# Flexy.net
KiCad netlist of a schematic drawn in Altium Designer
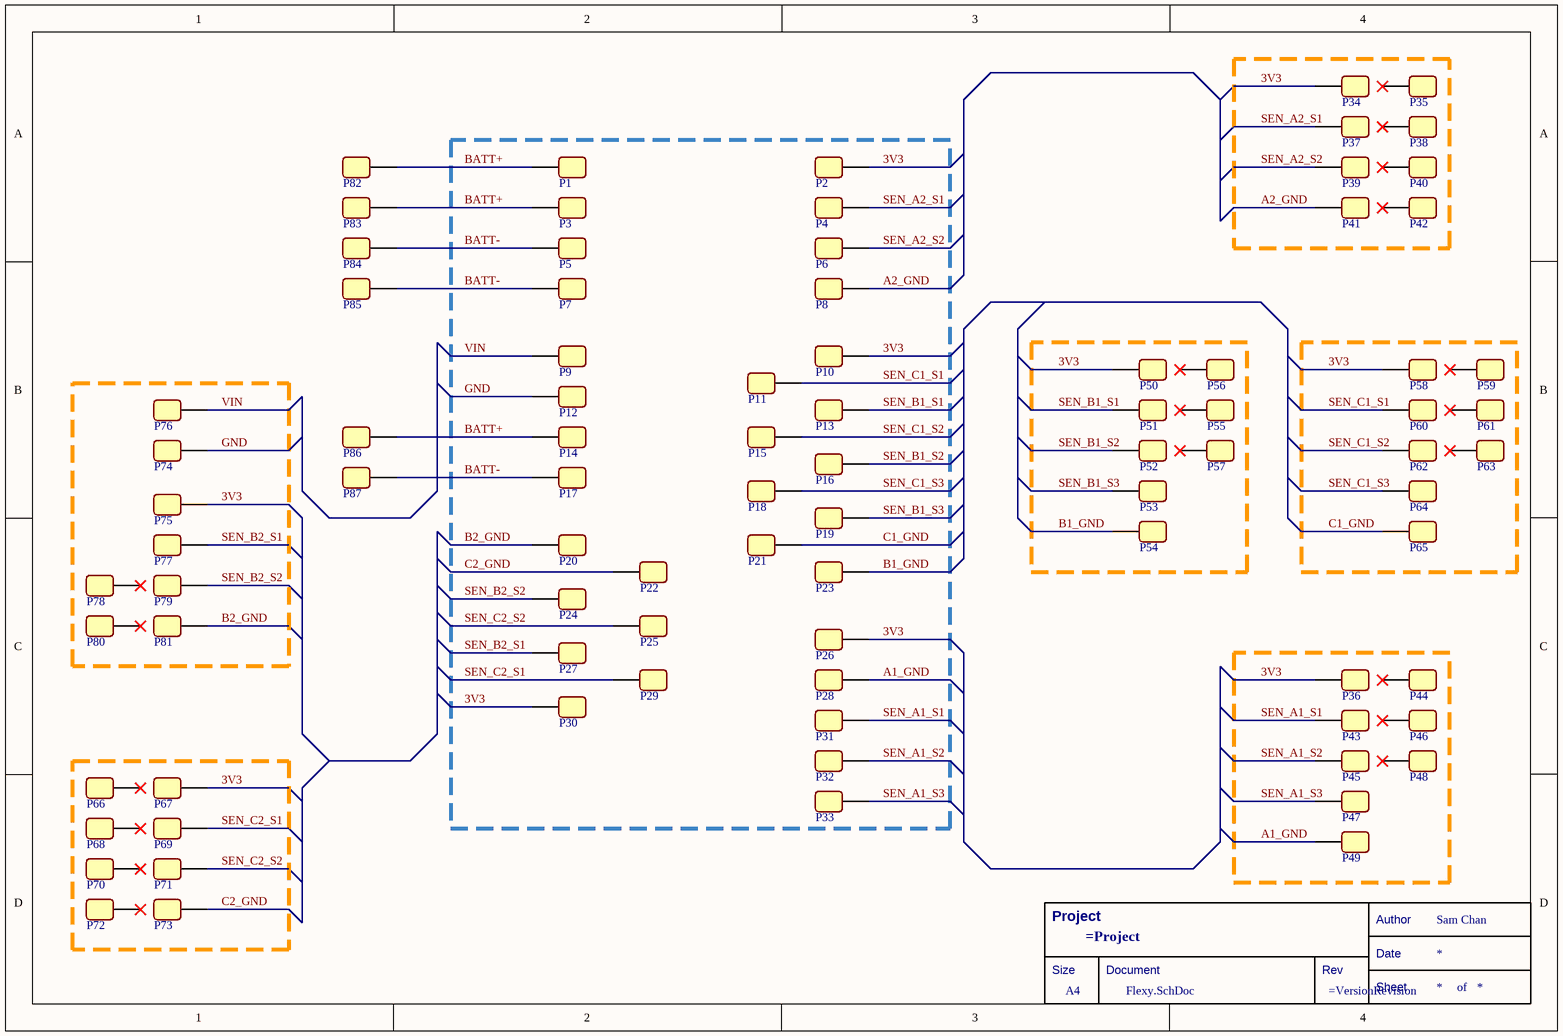
[diagram p0: Flexy.SchDoc]

(export (version "E")
  (design (tool "Eeschema 10.0.6"))
  (components
    (comp (ref "*")
      (value "Title Block")
      (description "Standard Title Block")
      (libsource (lib "Cube Library") (part "Title Block"))
    )
    (comp (ref "P1")
      (value "PAD_4")
      (footprint "PAD_0.5X1MM")
      (description "a Rec pad, 0.5X1mm")
      (libsource (lib "Cube Library") (part "PAD_4"))
    )
    (comp (ref "P2")
      (value "PAD_4")
      (footprint "PAD_0.5X1MM")
      (description "a Rec pad, 0.5X1mm")
      (libsource (lib "Cube Library") (part "PAD_4"))
    )
    (comp (ref "P3")
      (value "PAD_4")
      (footprint "PAD_0.5X1MM")
      (description "a Rec pad, 0.5X1mm")
      (libsource (lib "Cube Library") (part "PAD_4"))
    )
    (comp (ref "P4")
      (value "PAD_4")
      (footprint "PAD_0.5X1MM")
      (description "a Rec pad, 0.5X1mm")
      (libsource (lib "Cube Library") (part "PAD_4"))
    )
    (comp (ref "P5")
      (value "PAD_4")
      (footprint "PAD_0.5X1MM")
      (description "a Rec pad, 0.5X1mm")
      (libsource (lib "Cube Library") (part "PAD_4"))
    )
    (comp (ref "P6")
      (value "PAD_4")
      (footprint "PAD_0.5X1MM")
      (description "a Rec pad, 0.5X1mm")
      (libsource (lib "Cube Library") (part "PAD_4"))
    )
    (comp (ref "P7")
      (value "PAD_4")
      (footprint "PAD_0.5X1MM")
      (description "a Rec pad, 0.5X1mm")
      (libsource (lib "Cube Library") (part "PAD_4"))
    )
    (comp (ref "P8")
      (value "PAD_4")
      (footprint "PAD_0.5X1MM")
      (description "a Rec pad, 0.5X1mm")
      (libsource (lib "Cube Library") (part "PAD_4"))
    )
    (comp (ref "P9")
      (value "PAD_4")
      (footprint "PAD_0.5X1MM")
      (description "a Rec pad, 0.5X1mm")
      (libsource (lib "Cube Library") (part "PAD_4"))
    )
    (comp (ref "P10")
      (value "PAD_4")
      (footprint "PAD_0.5X1MM")
      (description "a Rec pad, 0.5X1mm")
      (libsource (lib "Cube Library") (part "PAD_4"))
    )
    (comp (ref "P11")
      (value "PAD_4")
      (footprint "PAD_0.5X1MM")
      (description "a Rec pad, 0.5X1mm")
      (libsource (lib "Cube Library") (part "PAD_4"))
    )
    (comp (ref "P12")
      (value "PAD_4")
      (footprint "PAD_0.5X1MM")
      (description "a Rec pad, 0.5X1mm")
      (libsource (lib "Cube Library") (part "PAD_4"))
    )
    (comp (ref "P13")
      (value "PAD_4")
      (footprint "PAD_0.5X1MM")
      (description "a Rec pad, 0.5X1mm")
      (libsource (lib "Cube Library") (part "PAD_4"))
    )
    (comp (ref "P14")
      (value "PAD_4")
      (footprint "PAD_0.5X1MM")
      (description "a Rec pad, 0.5X1mm")
      (libsource (lib "Cube Library") (part "PAD_4"))
    )
    (comp (ref "P15")
      (value "PAD_4")
      (footprint "PAD_0.5X1MM")
      (description "a Rec pad, 0.5X1mm")
      (libsource (lib "Cube Library") (part "PAD_4"))
    )
    (comp (ref "P16")
      (value "PAD_4")
      (footprint "PAD_0.5X1MM")
      (description "a Rec pad, 0.5X1mm")
      (libsource (lib "Cube Library") (part "PAD_4"))
    )
    (comp (ref "P17")
      (value "PAD_4")
      (footprint "PAD_0.5X1MM")
      (description "a Rec pad, 0.5X1mm")
      (libsource (lib "Cube Library") (part "PAD_4"))
    )
    (comp (ref "P18")
      (value "PAD_4")
      (footprint "PAD_0.5X1MM")
      (description "a Rec pad, 0.5X1mm")
      (libsource (lib "Cube Library") (part "PAD_4"))
    )
    (comp (ref "P19")
      (value "PAD_4")
      (footprint "PAD_0.5X1MM")
      (description "a Rec pad, 0.5X1mm")
      (libsource (lib "Cube Library") (part "PAD_4"))
    )
    (comp (ref "P20")
      (value "PAD_4")
      (footprint "PAD_0.5X1MM")
      (description "a Rec pad, 0.5X1mm")
      (libsource (lib "Cube Library") (part "PAD_4"))
    )
    (comp (ref "P21")
      (value "PAD_4")
      (footprint "PAD_0.5X1MM")
      (description "a Rec pad, 0.5X1mm")
      (libsource (lib "Cube Library") (part "PAD_4"))
    )
    (comp (ref "P22")
      (value "PAD_4")
      (footprint "PAD_0.5X1MM")
      (description "a Rec pad, 0.5X1mm")
      (libsource (lib "Cube Library") (part "PAD_4"))
    )
    (comp (ref "P23")
      (value "PAD_4")
      (footprint "PAD_0.5X1MM")
      (description "a Rec pad, 0.5X1mm")
      (libsource (lib "Cube Library") (part "PAD_4"))
    )
    (comp (ref "P24")
      (value "PAD_4")
      (footprint "PAD_0.5X1MM")
      (description "a Rec pad, 0.5X1mm")
      (libsource (lib "Cube Library") (part "PAD_4"))
    )
    (comp (ref "P25")
      (value "PAD_4")
      (footprint "PAD_0.5X1MM")
      (description "a Rec pad, 0.5X1mm")
      (libsource (lib "Cube Library") (part "PAD_4"))
    )
    (comp (ref "P26")
      (value "PAD_4")
      (footprint "PAD_0.5X1MM")
      (description "a Rec pad, 0.5X1mm")
      (libsource (lib "Cube Library") (part "PAD_4"))
    )
    (comp (ref "P27")
      (value "PAD_4")
      (footprint "PAD_0.5X1MM")
      (description "a Rec pad, 0.5X1mm")
      (libsource (lib "Cube Library") (part "PAD_4"))
    )
    (comp (ref "P28")
      (value "PAD_4")
      (footprint "PAD_0.5X1MM")
      (description "a Rec pad, 0.5X1mm")
      (libsource (lib "Cube Library") (part "PAD_4"))
    )
    (comp (ref "P29")
      (value "PAD_4")
      (footprint "PAD_0.5X1MM")
      (description "a Rec pad, 0.5X1mm")
      (libsource (lib "Cube Library") (part "PAD_4"))
    )
    (comp (ref "P30")
      (value "PAD_4")
      (footprint "PAD_0.5X1MM")
      (description "a Rec pad, 0.5X1mm")
      (libsource (lib "Cube Library") (part "PAD_4"))
    )
    (comp (ref "P31")
      (value "PAD_4")
      (footprint "PAD_0.5X1MM")
      (description "a Rec pad, 0.5X1mm")
      (libsource (lib "Cube Library") (part "PAD_4"))
    )
    (comp (ref "P32")
      (value "PAD_4")
      (footprint "PAD_0.5X1MM")
      (description "a Rec pad, 0.5X1mm")
      (libsource (lib "Cube Library") (part "PAD_4"))
    )
    (comp (ref "P33")
      (value "PAD_4")
      (footprint "PAD_0.5X1MM")
      (description "a Rec pad, 0.5X1mm")
      (libsource (lib "Cube Library") (part "PAD_4"))
    )
    (comp (ref "P34")
      (value "PAD_4")
      (footprint "PAD_0.5X1MM")
      (description "a Rec pad, 0.5X1mm")
      (libsource (lib "Cube Library") (part "PAD_4"))
    )
    (comp (ref "P35")
      (value "PAD_4")
      (footprint "PAD_0.5X1MM")
      (description "a Rec pad, 0.5X1mm")
      (libsource (lib "Cube Library") (part "PAD_4"))
    )
    (comp (ref "P36")
      (value "PAD_4")
      (footprint "PAD_0.5X1MM")
      (description "a Rec pad, 0.5X1mm")
      (libsource (lib "Cube Library") (part "PAD_4"))
    )
    (comp (ref "P37")
      (value "PAD_4")
      (footprint "PAD_0.5X1MM")
      (description "a Rec pad, 0.5X1mm")
      (libsource (lib "Cube Library") (part "PAD_4"))
    )
    (comp (ref "P38")
      (value "PAD_4")
      (footprint "PAD_0.5X1MM")
      (description "a Rec pad, 0.5X1mm")
      (libsource (lib "Cube Library") (part "PAD_4"))
    )
    (comp (ref "P39")
      (value "PAD_4")
      (footprint "PAD_0.5X1MM")
      (description "a Rec pad, 0.5X1mm")
      (libsource (lib "Cube Library") (part "PAD_4"))
    )
    (comp (ref "P40")
      (value "PAD_4")
      (footprint "PAD_0.5X1MM")
      (description "a Rec pad, 0.5X1mm")
      (libsource (lib "Cube Library") (part "PAD_4"))
    )
    (comp (ref "P41")
      (value "PAD_4")
      (footprint "PAD_0.5X1MM")
      (description "a Rec pad, 0.5X1mm")
      (libsource (lib "Cube Library") (part "PAD_4"))
    )
    (comp (ref "P42")
      (value "PAD_4")
      (footprint "PAD_0.5X1MM")
      (description "a Rec pad, 0.5X1mm")
      (libsource (lib "Cube Library") (part "PAD_4"))
    )
    (comp (ref "P43")
      (value "PAD_4")
      (footprint "PAD_0.5X1MM")
      (description "a Rec pad, 0.5X1mm")
      (libsource (lib "Cube Library") (part "PAD_4"))
    )
    (comp (ref "P44")
      (value "PAD_4")
      (footprint "PAD_0.5X1MM")
      (description "a Rec pad, 0.5X1mm")
      (libsource (lib "Cube Library") (part "PAD_4"))
    )
    (comp (ref "P45")
      (value "PAD_4")
      (footprint "PAD_0.5X1MM")
      (description "a Rec pad, 0.5X1mm")
      (libsource (lib "Cube Library") (part "PAD_4"))
    )
    (comp (ref "P46")
      (value "PAD_4")
      (footprint "PAD_0.5X1MM")
      (description "a Rec pad, 0.5X1mm")
      (libsource (lib "Cube Library") (part "PAD_4"))
    )
    (comp (ref "P47")
      (value "PAD_4")
      (footprint "PAD_0.5X1MM")
      (description "a Rec pad, 0.5X1mm")
      (libsource (lib "Cube Library") (part "PAD_4"))
    )
    (comp (ref "P48")
      (value "PAD_4")
      (footprint "PAD_0.5X1MM")
      (description "a Rec pad, 0.5X1mm")
      (libsource (lib "Cube Library") (part "PAD_4"))
    )
    (comp (ref "P49")
      (value "PAD_4")
      (footprint "PAD_0.5X1MM")
      (description "a Rec pad, 0.5X1mm")
      (libsource (lib "Cube Library") (part "PAD_4"))
    )
    (comp (ref "P50")
      (value "PAD_4")
      (footprint "PAD_0.5X1MM")
      (description "a Rec pad, 0.5X1mm")
      (libsource (lib "Cube Library") (part "PAD_4"))
    )
    (comp (ref "P51")
      (value "PAD_4")
      (footprint "PAD_0.5X1MM")
      (description "a Rec pad, 0.5X1mm")
      (libsource (lib "Cube Library") (part "PAD_4"))
    )
    (comp (ref "P52")
      (value "PAD_4")
      (footprint "PAD_0.5X1MM")
      (description "a Rec pad, 0.5X1mm")
      (libsource (lib "Cube Library") (part "PAD_4"))
    )
    (comp (ref "P53")
      (value "PAD_4")
      (footprint "PAD_0.5X1MM")
      (description "a Rec pad, 0.5X1mm")
      (libsource (lib "Cube Library") (part "PAD_4"))
    )
    (comp (ref "P54")
      (value "PAD_4")
      (footprint "PAD_0.5X1MM")
      (description "a Rec pad, 0.5X1mm")
      (libsource (lib "Cube Library") (part "PAD_4"))
    )
    (comp (ref "P55")
      (value "PAD_4")
      (footprint "PAD_0.5X1MM")
      (description "a Rec pad, 0.5X1mm")
      (libsource (lib "Cube Library") (part "PAD_4"))
    )
    (comp (ref "P56")
      (value "PAD_4")
      (footprint "PAD_0.5X1MM")
      (description "a Rec pad, 0.5X1mm")
      (libsource (lib "Cube Library") (part "PAD_4"))
    )
    (comp (ref "P57")
      (value "PAD_4")
      (footprint "PAD_0.5X1MM")
      (description "a Rec pad, 0.5X1mm")
      (libsource (lib "Cube Library") (part "PAD_4"))
    )
    (comp (ref "P58")
      (value "PAD_4")
      (footprint "PAD_0.5X1MM")
      (description "a Rec pad, 0.5X1mm")
      (libsource (lib "Cube Library") (part "PAD_4"))
    )
    (comp (ref "P59")
      (value "PAD_4")
      (footprint "PAD_0.5X1MM")
      (description "a Rec pad, 0.5X1mm")
      (libsource (lib "Cube Library") (part "PAD_4"))
    )
    (comp (ref "P60")
      (value "PAD_4")
      (footprint "PAD_0.5X1MM")
      (description "a Rec pad, 0.5X1mm")
      (libsource (lib "Cube Library") (part "PAD_4"))
    )
    (comp (ref "P61")
      (value "PAD_4")
      (footprint "PAD_0.5X1MM")
      (description "a Rec pad, 0.5X1mm")
      (libsource (lib "Cube Library") (part "PAD_4"))
    )
    (comp (ref "P62")
      (value "PAD_4")
      (footprint "PAD_0.5X1MM")
      (description "a Rec pad, 0.5X1mm")
      (libsource (lib "Cube Library") (part "PAD_4"))
    )
    (comp (ref "P63")
      (value "PAD_4")
      (footprint "PAD_0.5X1MM")
      (description "a Rec pad, 0.5X1mm")
      (libsource (lib "Cube Library") (part "PAD_4"))
    )
    (comp (ref "P64")
      (value "PAD_4")
      (footprint "PAD_0.5X1MM")
      (description "a Rec pad, 0.5X1mm")
      (libsource (lib "Cube Library") (part "PAD_4"))
    )
    (comp (ref "P65")
      (value "PAD_4")
      (footprint "PAD_0.5X1MM")
      (description "a Rec pad, 0.5X1mm")
      (libsource (lib "Cube Library") (part "PAD_4"))
    )
    (comp (ref "P66")
      (value "PAD_4")
      (footprint "PAD_0.5X1MM")
      (description "a Rec pad, 0.5X1mm")
      (libsource (lib "Cube Library") (part "PAD_4"))
    )
    (comp (ref "P67")
      (value "PAD_4")
      (footprint "PAD_0.5X1MM")
      (description "a Rec pad, 0.5X1mm")
      (libsource (lib "Cube Library") (part "PAD_4"))
    )
    (comp (ref "P68")
      (value "PAD_4")
      (footprint "PAD_0.5X1MM")
      (description "a Rec pad, 0.5X1mm")
      (libsource (lib "Cube Library") (part "PAD_4"))
    )
    (comp (ref "P69")
      (value "PAD_4")
      (footprint "PAD_0.5X1MM")
      (description "a Rec pad, 0.5X1mm")
      (libsource (lib "Cube Library") (part "PAD_4"))
    )
    (comp (ref "P70")
      (value "PAD_4")
      (footprint "PAD_0.5X1MM")
      (description "a Rec pad, 0.5X1mm")
      (libsource (lib "Cube Library") (part "PAD_4"))
    )
    (comp (ref "P71")
      (value "PAD_4")
      (footprint "PAD_0.5X1MM")
      (description "a Rec pad, 0.5X1mm")
      (libsource (lib "Cube Library") (part "PAD_4"))
    )
    (comp (ref "P72")
      (value "PAD_4")
      (footprint "PAD_0.5X1MM")
      (description "a Rec pad, 0.5X1mm")
      (libsource (lib "Cube Library") (part "PAD_4"))
    )
    (comp (ref "P73")
      (value "PAD_4")
      (footprint "PAD_0.5X1MM")
      (description "a Rec pad, 0.5X1mm")
      (libsource (lib "Cube Library") (part "PAD_4"))
    )
    (comp (ref "P74")
      (value "PAD_4")
      (footprint "PAD_0.5X1MM")
      (description "a Rec pad, 0.5X1mm")
      (libsource (lib "Cube Library") (part "PAD_4"))
    )
    (comp (ref "P75")
      (value "PAD_4")
      (footprint "PAD_0.5X1MM")
      (description "a Rec pad, 0.5X1mm")
      (libsource (lib "Cube Library") (part "PAD_4"))
    )
    (comp (ref "P76")
      (value "PAD_4")
      (footprint "PAD_0.5X1MM")
      (description "a Rec pad, 0.5X1mm")
      (libsource (lib "Cube Library") (part "PAD_4"))
    )
    (comp (ref "P77")
      (value "PAD_4")
      (footprint "PAD_0.5X1MM")
      (description "a Rec pad, 0.5X1mm")
      (libsource (lib "Cube Library") (part "PAD_4"))
    )
    (comp (ref "P78")
      (value "PAD_4")
      (footprint "PAD_0.5X1MM")
      (description "a Rec pad, 0.5X1mm")
      (libsource (lib "Cube Library") (part "PAD_4"))
    )
    (comp (ref "P79")
      (value "PAD_4")
      (footprint "PAD_0.5X1MM")
      (description "a Rec pad, 0.5X1mm")
      (libsource (lib "Cube Library") (part "PAD_4"))
    )
    (comp (ref "P80")
      (value "PAD_4")
      (footprint "PAD_0.5X1MM")
      (description "a Rec pad, 0.5X1mm")
      (libsource (lib "Cube Library") (part "PAD_4"))
    )
    (comp (ref "P81")
      (value "PAD_4")
      (footprint "PAD_0.5X1MM")
      (description "a Rec pad, 0.5X1mm")
      (libsource (lib "Cube Library") (part "PAD_4"))
    )
    (comp (ref "P82")
      (value "PAD_4")
      (footprint "PAD_0.5X1MM")
      (description "a Rec pad, 0.5X1mm")
      (libsource (lib "Cube Library") (part "PAD_4"))
    )
    (comp (ref "P83")
      (value "PAD_4")
      (footprint "PAD_0.5X1MM")
      (description "a Rec pad, 0.5X1mm")
      (libsource (lib "Cube Library") (part "PAD_4"))
    )
    (comp (ref "P84")
      (value "PAD_4")
      (footprint "PAD_0.5X1MM")
      (description "a Rec pad, 0.5X1mm")
      (libsource (lib "Cube Library") (part "PAD_4"))
    )
    (comp (ref "P85")
      (value "PAD_4")
      (footprint "PAD_0.5X1MM")
      (description "a Rec pad, 0.5X1mm")
      (libsource (lib "Cube Library") (part "PAD_4"))
    )
    (comp (ref "P86")
      (value "PAD_4")
      (footprint "PAD_0.5X1MM")
      (description "a Rec pad, 0.5X1mm")
      (libsource (lib "Cube Library") (part "PAD_4"))
    )
    (comp (ref "P87")
      (value "PAD_4")
      (footprint "PAD_0.5X1MM")
      (description "a Rec pad, 0.5X1mm")
      (libsource (lib "Cube Library") (part "PAD_4"))
    )
  )
  (nets
    (net (code "1") (name "/3V3") (class "Default")
      (node (ref "P10") (pin "1") (pinfunction "1_1") (pintype "passive"))
      (node (ref "P2") (pin "1") (pinfunction "1_1") (pintype "passive"))
      (node (ref "P26") (pin "1") (pinfunction "1_1") (pintype "passive"))
      (node (ref "P30") (pin "1") (pinfunction "1_1") (pintype "passive"))
      (node (ref "P34") (pin "1") (pinfunction "1_1") (pintype "passive"))
      (node (ref "P36") (pin "1") (pinfunction "1_1") (pintype "passive"))
      (node (ref "P50") (pin "1") (pinfunction "1_1") (pintype "passive"))
      (node (ref "P58") (pin "1") (pinfunction "1_1") (pintype "passive"))
      (node (ref "P67") (pin "1") (pinfunction "1_1") (pintype "passive"))
      (node (ref "P75") (pin "1") (pinfunction "1_1") (pintype "passive"))
    )
    (net (code "2") (name "/A1_GND") (class "Default")
      (node (ref "P28") (pin "1") (pinfunction "1_1") (pintype "passive"))
      (node (ref "P49") (pin "1") (pinfunction "1_1") (pintype "passive"))
    )
    (net (code "3") (name "/A2_GND") (class "Default")
      (node (ref "P41") (pin "1") (pinfunction "1_1") (pintype "passive"))
      (node (ref "P8") (pin "1") (pinfunction "1_1") (pintype "passive"))
    )
    (net (code "4") (name "/B1_GND") (class "Default")
      (node (ref "P23") (pin "1") (pinfunction "1_1") (pintype "passive"))
      (node (ref "P54") (pin "1") (pinfunction "1_1") (pintype "passive"))
    )
    (net (code "5") (name "/B2_GND") (class "Default")
      (node (ref "P20") (pin "1") (pinfunction "1_1") (pintype "passive"))
      (node (ref "P81") (pin "1") (pinfunction "1_1") (pintype "passive"))
    )
    (net (code "6") (name "/BATT+") (class "Default")
      (node (ref "P1") (pin "1") (pinfunction "1_1") (pintype "passive"))
      (node (ref "P14") (pin "1") (pinfunction "1_1") (pintype "passive"))
      (node (ref "P3") (pin "1") (pinfunction "1_1") (pintype "passive"))
      (node (ref "P82") (pin "1") (pinfunction "1_1") (pintype "passive"))
      (node (ref "P83") (pin "1") (pinfunction "1_1") (pintype "passive"))
      (node (ref "P86") (pin "1") (pinfunction "1_1") (pintype "passive"))
    )
    (net (code "7") (name "/BATT-") (class "Default")
      (node (ref "P17") (pin "1") (pinfunction "1_1") (pintype "passive"))
      (node (ref "P5") (pin "1") (pinfunction "1_1") (pintype "passive"))
      (node (ref "P7") (pin "1") (pinfunction "1_1") (pintype "passive"))
      (node (ref "P84") (pin "1") (pinfunction "1_1") (pintype "passive"))
      (node (ref "P85") (pin "1") (pinfunction "1_1") (pintype "passive"))
      (node (ref "P87") (pin "1") (pinfunction "1_1") (pintype "passive"))
    )
    (net (code "8") (name "/C1_GND") (class "Default")
      (node (ref "P21") (pin "1") (pinfunction "1_1") (pintype "passive"))
      (node (ref "P65") (pin "1") (pinfunction "1_1") (pintype "passive"))
    )
    (net (code "9") (name "/C2_GND") (class "Default")
      (node (ref "P22") (pin "1") (pinfunction "1_1") (pintype "passive"))
      (node (ref "P73") (pin "1") (pinfunction "1_1") (pintype "passive"))
    )
    (net (code "10") (name "/GND") (class "Default")
      (node (ref "P12") (pin "1") (pinfunction "1_1") (pintype "passive"))
      (node (ref "P74") (pin "1") (pinfunction "1_1") (pintype "passive"))
    )
    (net (code "11") (name "/SEN_A1_S1") (class "Default")
      (node (ref "P31") (pin "1") (pinfunction "1_1") (pintype "passive"))
      (node (ref "P43") (pin "1") (pinfunction "1_1") (pintype "passive"))
    )
    (net (code "12") (name "/SEN_A1_S2") (class "Default")
      (node (ref "P32") (pin "1") (pinfunction "1_1") (pintype "passive"))
      (node (ref "P45") (pin "1") (pinfunction "1_1") (pintype "passive"))
    )
    (net (code "13") (name "/SEN_A1_S3") (class "Default")
      (node (ref "P33") (pin "1") (pinfunction "1_1") (pintype "passive"))
      (node (ref "P47") (pin "1") (pinfunction "1_1") (pintype "passive"))
    )
    (net (code "14") (name "/SEN_A2_S1") (class "Default")
      (node (ref "P37") (pin "1") (pinfunction "1_1") (pintype "passive"))
      (node (ref "P4") (pin "1") (pinfunction "1_1") (pintype "passive"))
    )
    (net (code "15") (name "/SEN_A2_S2") (class "Default")
      (node (ref "P39") (pin "1") (pinfunction "1_1") (pintype "passive"))
      (node (ref "P6") (pin "1") (pinfunction "1_1") (pintype "passive"))
    )
    (net (code "16") (name "/SEN_B1_S1") (class "Default")
      (node (ref "P13") (pin "1") (pinfunction "1_1") (pintype "passive"))
      (node (ref "P51") (pin "1") (pinfunction "1_1") (pintype "passive"))
    )
    (net (code "17") (name "/SEN_B1_S2") (class "Default")
      (node (ref "P16") (pin "1") (pinfunction "1_1") (pintype "passive"))
      (node (ref "P52") (pin "1") (pinfunction "1_1") (pintype "passive"))
    )
    (net (code "18") (name "/SEN_B1_S3") (class "Default")
      (node (ref "P19") (pin "1") (pinfunction "1_1") (pintype "passive"))
      (node (ref "P53") (pin "1") (pinfunction "1_1") (pintype "passive"))
    )
    (net (code "19") (name "/SEN_B2_S1") (class "Default")
      (node (ref "P27") (pin "1") (pinfunction "1_1") (pintype "passive"))
      (node (ref "P77") (pin "1") (pinfunction "1_1") (pintype "passive"))
    )
    (net (code "20") (name "/SEN_B2_S2") (class "Default")
      (node (ref "P24") (pin "1") (pinfunction "1_1") (pintype "passive"))
      (node (ref "P79") (pin "1") (pinfunction "1_1") (pintype "passive"))
    )
    (net (code "21") (name "/SEN_C1_S1") (class "Default")
      (node (ref "P11") (pin "1") (pinfunction "1_1") (pintype "passive"))
      (node (ref "P60") (pin "1") (pinfunction "1_1") (pintype "passive"))
    )
    (net (code "22") (name "/SEN_C1_S2") (class "Default")
      (node (ref "P15") (pin "1") (pinfunction "1_1") (pintype "passive"))
      (node (ref "P62") (pin "1") (pinfunction "1_1") (pintype "passive"))
    )
    (net (code "23") (name "/SEN_C1_S3") (class "Default")
      (node (ref "P18") (pin "1") (pinfunction "1_1") (pintype "passive"))
      (node (ref "P64") (pin "1") (pinfunction "1_1") (pintype "passive"))
    )
    (net (code "24") (name "/SEN_C2_S1") (class "Default")
      (node (ref "P29") (pin "1") (pinfunction "1_1") (pintype "passive"))
      (node (ref "P69") (pin "1") (pinfunction "1_1") (pintype "passive"))
    )
    (net (code "25") (name "/SEN_C2_S2") (class "Default")
      (node (ref "P25") (pin "1") (pinfunction "1_1") (pintype "passive"))
      (node (ref "P71") (pin "1") (pinfunction "1_1") (pintype "passive"))
    )
    (net (code "26") (name "/VIN") (class "Default")
      (node (ref "P76") (pin "1") (pinfunction "1_1") (pintype "passive"))
      (node (ref "P9") (pin "1") (pinfunction "1_1") (pintype "passive"))
    )
    (net (code "27") (name "unconnected-(P35-Pad1)") (class "Default")
      (node (ref "P35") (pin "1") (pinfunction "1_1") (pintype "passive+no_connect"))
    )
    (net (code "28") (name "unconnected-(P38-Pad1)") (class "Default")
      (node (ref "P38") (pin "1") (pinfunction "1_1") (pintype "passive+no_connect"))
    )
    (net (code "29") (name "unconnected-(P40-Pad1)") (class "Default")
      (node (ref "P40") (pin "1") (pinfunction "1_1") (pintype "passive+no_connect"))
    )
    (net (code "30") (name "unconnected-(P42-Pad1)") (class "Default")
      (node (ref "P42") (pin "1") (pinfunction "1_1") (pintype "passive+no_connect"))
    )
    (net (code "31") (name "unconnected-(P44-Pad1)") (class "Default")
      (node (ref "P44") (pin "1") (pinfunction "1_1") (pintype "passive+no_connect"))
    )
    (net (code "32") (name "unconnected-(P46-Pad1)") (class "Default")
      (node (ref "P46") (pin "1") (pinfunction "1_1") (pintype "passive+no_connect"))
    )
    (net (code "33") (name "unconnected-(P48-Pad1)") (class "Default")
      (node (ref "P48") (pin "1") (pinfunction "1_1") (pintype "passive+no_connect"))
    )
    (net (code "34") (name "unconnected-(P55-Pad1)") (class "Default")
      (node (ref "P55") (pin "1") (pinfunction "1_1") (pintype "passive+no_connect"))
    )
    (net (code "35") (name "unconnected-(P56-Pad1)") (class "Default")
      (node (ref "P56") (pin "1") (pinfunction "1_1") (pintype "passive+no_connect"))
    )
    (net (code "36") (name "unconnected-(P57-Pad1)") (class "Default")
      (node (ref "P57") (pin "1") (pinfunction "1_1") (pintype "passive+no_connect"))
    )
    (net (code "37") (name "unconnected-(P59-Pad1)") (class "Default")
      (node (ref "P59") (pin "1") (pinfunction "1_1") (pintype "passive+no_connect"))
    )
    (net (code "38") (name "unconnected-(P61-Pad1)") (class "Default")
      (node (ref "P61") (pin "1") (pinfunction "1_1") (pintype "passive+no_connect"))
    )
    (net (code "39") (name "unconnected-(P63-Pad1)") (class "Default")
      (node (ref "P63") (pin "1") (pinfunction "1_1") (pintype "passive+no_connect"))
    )
    (net (code "40") (name "unconnected-(P66-Pad1)") (class "Default")
      (node (ref "P66") (pin "1") (pinfunction "1_1") (pintype "passive+no_connect"))
    )
    (net (code "41") (name "unconnected-(P68-Pad1)") (class "Default")
      (node (ref "P68") (pin "1") (pinfunction "1_1") (pintype "passive+no_connect"))
    )
    (net (code "42") (name "unconnected-(P70-Pad1)") (class "Default")
      (node (ref "P70") (pin "1") (pinfunction "1_1") (pintype "passive+no_connect"))
    )
    (net (code "43") (name "unconnected-(P72-Pad1)") (class "Default")
      (node (ref "P72") (pin "1") (pinfunction "1_1") (pintype "passive+no_connect"))
    )
    (net (code "44") (name "unconnected-(P78-Pad1)") (class "Default")
      (node (ref "P78") (pin "1") (pinfunction "1_1") (pintype "passive+no_connect"))
    )
    (net (code "45") (name "unconnected-(P80-Pad1)") (class "Default")
      (node (ref "P80") (pin "1") (pinfunction "1_1") (pintype "passive+no_connect"))
    )
  )
)
